# Main.net
KiCad netlist of a schematic drawn in Altium Designer
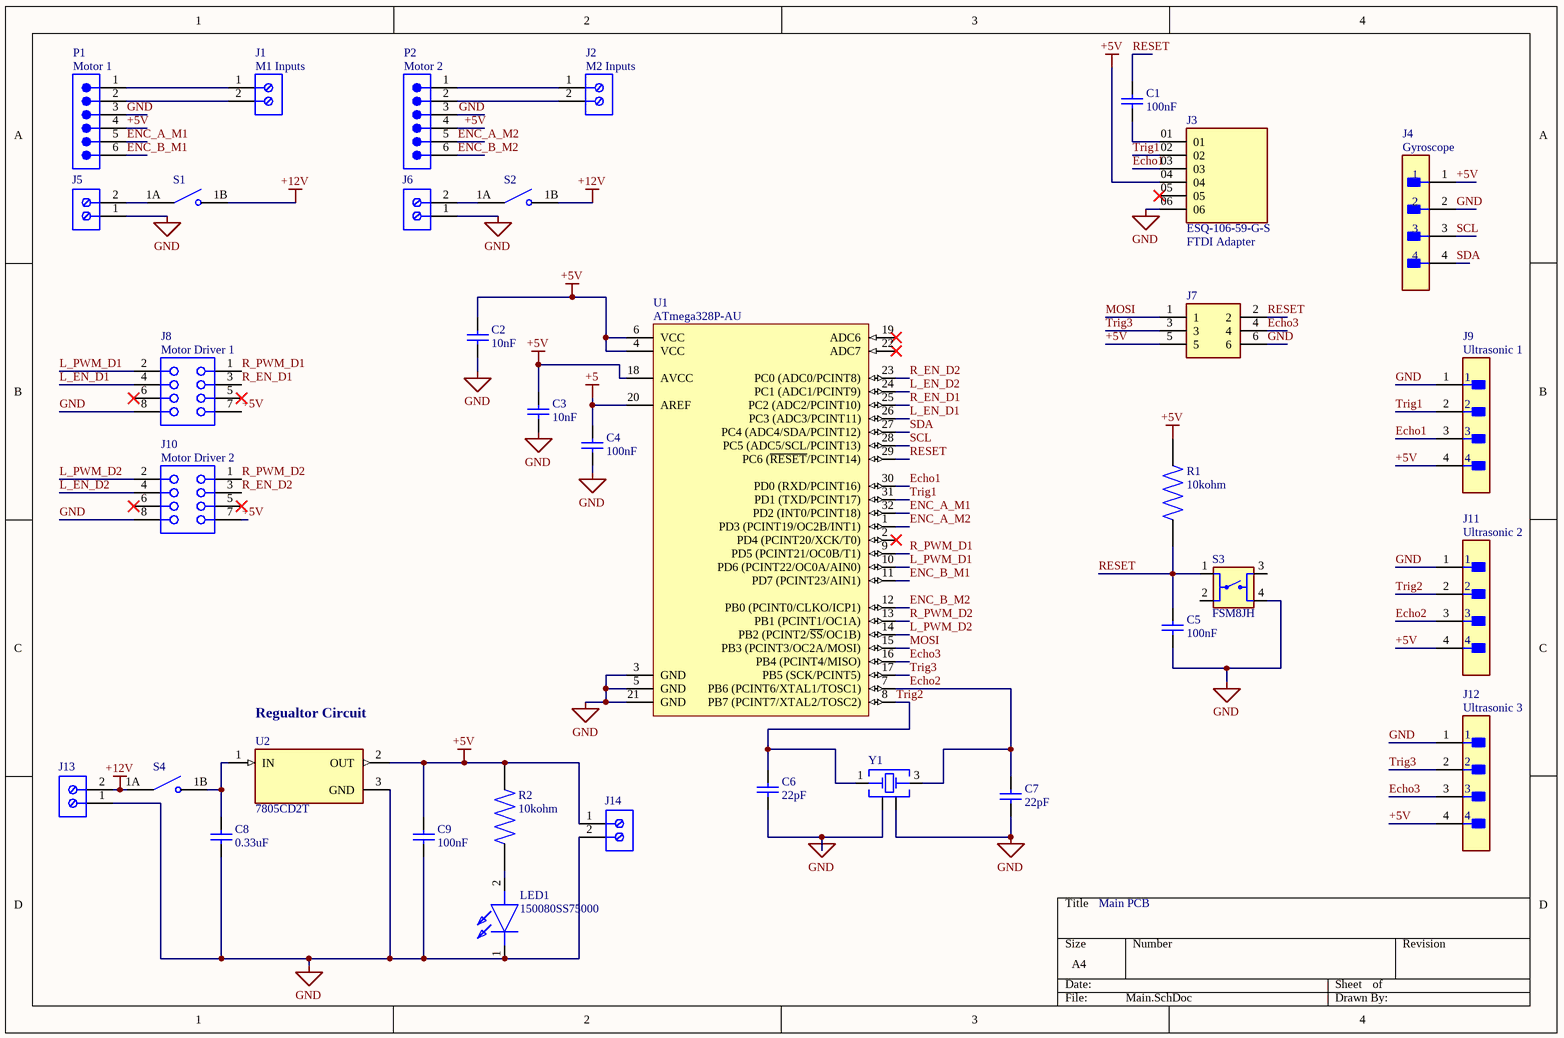
[diagram p0: Main.SchDoc]

(export (version "E")
  (design (tool "Eeschema 10.0.6"))
  (components
    (comp (ref "C1")
      (value "100nF")
      (footprint "WCAP-CSST_0603_L1.6W0.8H0.8_Reflow")
      (fields
        (field (name "MANUFACTURER PART NUMBER") "885382206004")
        (field (name "MANUFACTURER") "Wurth Elektronik")
      )
      (libsource (lib "Altium_WCAP-CSST_rev24a") (part "885382206004"))
    )
    (comp (ref "C2")
      (value "10nF")
      (footprint "WCAP-CSST_0603_L1.6W0.8H0.8_Reflow")
      (fields
        (field (name "MANUFACTURER PART NUMBER") "885382206002")
        (field (name "MANUFACTURER") "Wurth Elektronik")
      )
      (libsource (lib "Altium_WCAP-CSST_rev24a") (part "885382206002"))
    )
    (comp (ref "C3")
      (value "10nF")
      (footprint "WCAP-CSST_0603_L1.6W0.8H0.8_Reflow")
      (fields
        (field (name "MANUFACTURER PART NUMBER") "885382206002")
        (field (name "MANUFACTURER") "Wurth Elektronik")
      )
      (libsource (lib "Altium_WCAP-CSST_rev24a") (part "885382206002"))
    )
    (comp (ref "C4")
      (value "100nF")
      (footprint "WCAP-CSST_0603_L1.6W0.8H0.8_Reflow")
      (fields
        (field (name "MANUFACTURER PART NUMBER") "885382206004")
        (field (name "MANUFACTURER") "Wurth Elektronik")
      )
      (libsource (lib "Altium_WCAP-CSST_rev24a") (part "885382206004"))
    )
    (comp (ref "C5")
      (value "100nF")
      (footprint "WCAP-CSST_0603_L1.6W0.8H0.8_Reflow")
      (fields
        (field (name "MANUFACTURER PART NUMBER") "885382206004")
        (field (name "MANUFACTURER") "Wurth Elektronik")
      )
      (libsource (lib "Altium_WCAP-CSST_rev24a") (part "885382206004"))
    )
    (comp (ref "C6")
      (value "22pF")
      (footprint "WCAP-CSGP_0603_L1.6W0.8H0.8_Reflow")
      (description "WCAP-CSGP Multilayer Ceramic Chip Capacitor, General Purpose, size 0603, NP0, 22pF, 10VDC")
      (fields
        (field (name "MANUFACTURER PART NUMBER") "885012006004")
        (field (name "MANUFACTURER") "Wurth Elektronik")
      )
      (libsource (lib "Altium_WCAP-CSGP_rev24b") (part "885012006004"))
    )
    (comp (ref "C7")
      (value "22pF")
      (footprint "WCAP-CSGP_0603_L1.6W0.8H0.8_Reflow")
      (description "WCAP-CSGP Multilayer Ceramic Chip Capacitor, General Purpose, size 0603, NP0, 22pF, 10VDC")
      (fields
        (field (name "MANUFACTURER PART NUMBER") "885012006004")
        (field (name "MANUFACTURER") "Wurth Elektronik")
      )
      (libsource (lib "Altium_WCAP-CSGP_rev24b") (part "885012006004"))
    )
    (comp (ref "C8")
      (value "100nF")
      (footprint "WCAP-CSST_0603_L1.6W0.8H0.8_Reflow")
      (fields
        (field (name "MANUFACTURER PART NUMBER") "885382206004")
        (field (name "MANUFACTURER") "Wurth Elektronik")
        (field (name "CAPACITANCE") "0.33uF")
      )
      (libsource (lib "Altium_WCAP-CSST_rev24a") (part "885382206004"))
    )
    (comp (ref "C9")
      (value "100nF")
      (footprint "WCAP-CSST_0603_L1.6W0.8H0.8_Reflow")
      (fields
        (field (name "MANUFACTURER PART NUMBER") "885382206004")
        (field (name "MANUFACTURER") "Wurth Elektronik")
        (field (name "CAPACITANCE") "100nF")
      )
      (libsource (lib "Altium_WCAP-CSST_rev24a") (part "885382206004"))
    )
    (comp (ref "J1")
      (value "691137710002")
      (footprint "691137710002")
      (libsource (lib "Altium Content Vault") (part "TBL - 1R - 02P - Screw"))
    )
    (comp (ref "J2")
      (value "691137710002")
      (footprint "691137710002")
      (libsource (lib "Altium Content Vault") (part "TBL - 1R - 02P - Screw"))
    )
    (comp (ref "J3")
      (value "ESQ-106-59-G-S")
      (footprint "SAMTEC_ESQ-106-59-G-S")
      (libsource (lib "ESQ-106-59-G-S") (part "ESQ-106-59-G-S"))
    )
    (comp (ref "J4")
      (value "MPU6050")
      (footprint "FP-M20-9990445-MFG")
      (description "M20-9990445 Conn Unshrouded Header HDR 4 POS 2.54mm Solder ST Thru-Hole Bulk/Loose")
      (libsource (lib "Altium Content Vault") (part "299a8cea1bdcbc3624fe62c390fa72c"))
    )
    (comp (ref "J5")
      (value "691137710002")
      (footprint "691137710002")
      (libsource (lib "Altium Content Vault") (part "TBL - 1R - 02P - Screw"))
    )
    (comp (ref "J6")
      (value "691137710002")
      (footprint "691137710002")
      (libsource (lib "Altium Content Vault") (part "TBL - 1R - 02P - Screw"))
    )
    (comp (ref "J7")
      (value "20021111-00006T4LF")
      (footprint "SamacSys:2002111100006T4LF")
      (description "Connector")
      (libsource (lib "*") (part "20021111-00006T4LF"))
    )
    (comp (ref "J8")
      (value "Motor Driver 1")
      (footprint "SMTC-SSW-104-02-X-D")
      (description "SQ Post Socket, Through-hole, Vertical, -55 to 125 degC, 2.54mm Pitch, 8-Pin, Female, RoHS")
      (fields (field (name "MANUFACTURER") "Samtec") (field (name "PARTNUMBER") "SSW-104-02-G-D"))
      (libsource (lib "Altium Content Vault") (part "SMTC-SSW-104-X-X-D"))
    )
    (comp (ref "J9")
      (value "Ultrasonic 1")
      (footprint "FP-B4B-XH-A_LF_SN-MFG")
      (description "CONN HEADER VERT 4POS 2.5MM")
      (libsource (lib "") (part "299a8cea1bdcbc3624fe62c390fa72c_1"))
    )
    (comp (ref "J10")
      (value "Motor Driver 2")
      (footprint "SMTC-SSW-104-02-X-D")
      (description "SQ Post Socket, Through-hole, Vertical, -55 to 125 degC, 2.54mm Pitch, 8-Pin, Female, RoHS")
      (fields (field (name "MANUFACTURER") "Samtec") (field (name "PARTNUMBER") "SSW-104-02-G-D"))
      (libsource (lib "Altium Content Vault") (part "SMTC-SSW-104-X-X-D"))
    )
    (comp (ref "J11")
      (value "Ultrasonic 2")
      (footprint "FP-B4B-XH-A_LF_SN-MFG")
      (description "CONN HEADER VERT 4POS 2.5MM")
      (libsource (lib "") (part "299a8cea1bdcbc3624fe62c390fa72c_1"))
    )
    (comp (ref "J12")
      (value "Ultrasonic 3")
      (footprint "FP-B4B-XH-A_LF_SN-MFG")
      (description "CONN HEADER VERT 4POS 2.5MM")
      (libsource (lib "") (part "299a8cea1bdcbc3624fe62c390fa72c_1"))
    )
    (comp (ref "J13")
      (value "691137710002")
      (footprint "691137710002")
      (libsource (lib "Altium Content Vault") (part "TBL - 1R - 02P - Screw"))
    )
    (comp (ref "J14")
      (value "691137710002")
      (footprint "691137710002")
      (libsource (lib "Altium Content Vault") (part "TBL - 1R - 02P - Screw"))
    )
    (comp (ref "LED1")
      (value "150080SS75000")
      (footprint "SamacSys:150080SS75000")
      (description "LED")
      (fields (field (name "MOUSER PART NUMBER") "710-150080SS75000"))
      (libsource (lib "*") (part "150080SS75000"))
    )
    (comp (ref "P1")
      (value "Motor 1")
      (footprint "61300611121")
      (libsource (lib "Altium Content Vault") (part "Header_Male_1R_06P"))
    )
    (comp (ref "P2")
      (value "Motor 2")
      (footprint "61300611121")
      (libsource (lib "Altium Content Vault") (part "Header_Male_1R_06P"))
    )
    (comp (ref "R1")
      (value "10kohm")
      (footprint "RESC2012X65N")
      (fields (field (name "MP") "RMCF0805FG10K0"))
      (libsource (lib "RMCF0805FG10K0") (part "RMCF0805FG10K0"))
    )
    (comp (ref "R2")
      (value "10kohm")
      (footprint "RESC2012X65N")
      (fields (field (name "MP") "RMCF0805FG10K0"))
      (libsource (lib "RMCF0805FG10K0") (part "RMCF0805FG10K0"))
    )
    (comp (ref "S1")
      (value "DS01-254-L-01BE")
      (footprint "SW_DS01-254-L-01BE")
      (description "1 Position, Through Hole, 2.54 mm Pitch, Raised Slide Actuator, Flat Bottom, Long Pin, DIP Switch")
      (fields (field (name "MF") "CUI Devices"))
      (libsource (lib "DS01-254-L-01BE") (part "DS01-254-L-01BE"))
    )
    (comp (ref "S2")
      (value "DS01-254-L-01BE")
      (footprint "SW_DS01-254-L-01BE")
      (description "1 Position, Through Hole, 2.54 mm Pitch, Raised Slide Actuator, Flat Bottom, Long Pin, DIP Switch")
      (fields (field (name "MF") "CUI Devices"))
      (libsource (lib "DS01-254-L-01BE") (part "DS01-254-L-01BE"))
    )
    (comp (ref "S3")
      (value "FSM8JH")
      (footprint "SW_FSM8JH")
      (description "Tactile Switch SPST-NO Top Actuated Through Hole")
      (fields (field (name "MF") "TE Connectivity"))
      (libsource (lib "FSM8JH") (part "FSM8JH"))
    )
    (comp (ref "S4")
      (value "DS01-254-L-01BE")
      (footprint "SW_DS01-254-L-01BE")
      (description "1 Position, Through Hole, 2.54 mm Pitch, Raised Slide Actuator, Flat Bottom, Long Pin, DIP Switch")
      (fields (field (name "MF") "CUI Devices"))
      (libsource (lib "DS01-254-L-01BE") (part "DS01-254-L-01BE"))
    )
    (comp (ref "U1")
      (value "ATmega328P-AU")
      (footprint "32A_M")
      (libsource (lib "Altium Content Vault") (part "MC-8B-ATM48-SQ32"))
    )
    (comp (ref "U2")
      (value "7805CD2T")
      (footprint "TO254P1542X460-3N")
      (description "Linear Voltage Regulator IC Positive Fixed 1 Output 1.5A D2PAK")
      (fields (field (name "MF") "STMicroelectronics"))
      (libsource (lib "7805CD2T") (part "7805CD2T"))
    )
    (comp (ref "Y1")
      (value "830072604")
      (footprint "WE-XTAL_CFPX-180")
      (description "830072604 WE-XTAL Quartz Crystal")
      (libsource (lib "Altium Content Vault") (part "WE-XTAL_CFPX-180"))
    )
  )
  (nets
    (net (code "1") (name "+5") (class "Default")
      (node (ref "C4") (pin "2") (pinfunction "2_2") (pintype "passive"))
      (node (ref "U1") (pin "20") (pinfunction "AREF_20") (pintype "passive"))
    )
    (net (code "2") (name "+5V") (class "Default")
      (node (ref "C2") (pin "2") (pinfunction "2_2") (pintype "passive"))
      (node (ref "C3") (pin "2") (pinfunction "2_2") (pintype "passive"))
      (node (ref "C9") (pin "2") (pinfunction "2_2") (pintype "passive"))
      (node (ref "J10") (pin "7") (pinfunction "7_7") (pintype "passive"))
      (node (ref "J11") (pin "4") (pinfunction "4_4") (pintype "passive"))
      (node (ref "J12") (pin "4") (pinfunction "4_4") (pintype "passive"))
      (node (ref "J14") (pin "1") (pinfunction "1_1") (pintype "passive"))
      (node (ref "J3") (pin "04") (pinfunction "04_04") (pintype "passive"))
      (node (ref "J4") (pin "1") (pinfunction "1_1") (pintype "passive"))
      (node (ref "J7") (pin "5") (pinfunction "5_5") (pintype "passive"))
      (node (ref "J8") (pin "7") (pinfunction "7_7") (pintype "passive"))
      (node (ref "J9") (pin "4") (pinfunction "4_4") (pintype "passive"))
      (node (ref "P1") (pin "4") (pinfunction "4_4") (pintype "passive"))
      (node (ref "P2") (pin "4") (pinfunction "4_4") (pintype "passive"))
      (node (ref "R1") (pin "2") (pinfunction "2_2") (pintype "passive"))
      (node (ref "R2") (pin "2") (pinfunction "2_2") (pintype "passive"))
      (node (ref "U1") (pin "18") (pinfunction "AVCC_18") (pintype "power_in"))
      (node (ref "U1") (pin "4") (pinfunction "VCC_4") (pintype "power_in"))
      (node (ref "U1") (pin "6") (pinfunction "VCC_6") (pintype "power_in"))
      (node (ref "U2") (pin "2") (pinfunction "OUT_2") (pintype "output"))
    )
    (net (code "3") (name "+12V") (class "Default")
      (node (ref "J13") (pin "2") (pinfunction "2_2") (pintype "passive"))
      (node (ref "S1") (pin "1B") (pinfunction "NO1_1B") (pintype "passive"))
      (node (ref "S2") (pin "1B") (pinfunction "NO1_1B") (pintype "passive"))
      (node (ref "S4") (pin "1A") (pinfunction "COM1_1A") (pintype "passive"))
    )
    (net (code "4") (name "/ENC_A_M1") (class "Default")
      (node (ref "P1") (pin "5") (pinfunction "5_5") (pintype "passive"))
      (node (ref "U1") (pin "32") (pinfunction "PD2_(INT0/PCINT18)_32") (pintype "bidirectional"))
    )
    (net (code "5") (name "/ENC_A_M2") (class "Default")
      (node (ref "P2") (pin "5") (pinfunction "5_5") (pintype "passive"))
      (node (ref "U1") (pin "1") (pinfunction "PD3_(PCINT19/OC2B/INT1)_1") (pintype "bidirectional"))
    )
    (net (code "6") (name "/ENC_B_M1") (class "Default")
      (node (ref "P1") (pin "6") (pinfunction "6_6") (pintype "passive"))
      (node (ref "U1") (pin "11") (pinfunction "PD7_(PCINT23/AIN1)_11") (pintype "bidirectional"))
    )
    (net (code "7") (name "/ENC_B_M2") (class "Default")
      (node (ref "P2") (pin "6") (pinfunction "6_6") (pintype "passive"))
      (node (ref "U1") (pin "12") (pinfunction "PB0_(PCINT0/CLKO/ICP1)_12") (pintype "bidirectional"))
    )
    (net (code "8") (name "/Echo1") (class "Default")
      (node (ref "J3") (pin "03") (pinfunction "03_03") (pintype "passive"))
      (node (ref "J9") (pin "3") (pinfunction "3_3") (pintype "passive"))
      (node (ref "U1") (pin "30") (pinfunction "PD0_(RXD/PCINT16)_30") (pintype "bidirectional"))
    )
    (net (code "9") (name "/Echo2") (class "Default")
      (node (ref "C7") (pin "2") (pinfunction "2_2") (pintype "passive"))
      (node (ref "J11") (pin "3") (pinfunction "3_3") (pintype "passive"))
      (node (ref "U1") (pin "7") (pinfunction "PB6_(PCINT6/XTAL1/TOSC1)_7") (pintype "bidirectional"))
      (node (ref "Y1") (pin "3") (pinfunction "Crystal_3") (pintype "passive"))
    )
    (net (code "10") (name "/Echo3") (class "Default")
      (node (ref "J12") (pin "3") (pinfunction "3_3") (pintype "passive"))
      (node (ref "J7") (pin "4") (pinfunction "4_4") (pintype "passive"))
      (node (ref "U1") (pin "16") (pinfunction "PB4_(PCINT4/MISO)_16") (pintype "bidirectional"))
    )
    (net (code "11") (name "/L_EN_D1") (class "Default")
      (node (ref "J8") (pin "4") (pinfunction "4_4") (pintype "passive"))
      (node (ref "U1") (pin "26") (pinfunction "PC3_(ADC3/PCINT11)_26") (pintype "bidirectional"))
    )
    (net (code "12") (name "/L_EN_D2") (class "Default")
      (node (ref "J10") (pin "4") (pinfunction "4_4") (pintype "passive"))
      (node (ref "U1") (pin "24") (pinfunction "PC1_(ADC1/PCINT9)_24") (pintype "bidirectional"))
    )
    (net (code "13") (name "/L_PWM_D1") (class "Default")
      (node (ref "J8") (pin "2") (pinfunction "2_2") (pintype "passive"))
      (node (ref "U1") (pin "10") (pinfunction "PD6_(PCINT22/OC0A/AIN0)_10") (pintype "bidirectional"))
    )
    (net (code "14") (name "/L_PWM_D2") (class "Default")
      (node (ref "J10") (pin "2") (pinfunction "2_2") (pintype "passive"))
      (node (ref "U1") (pin "14") (pinfunction "PB2_(PCINT2/~{SS}/OC1B)_14") (pintype "bidirectional"))
    )
    (net (code "15") (name "/MOSI") (class "Default")
      (node (ref "J7") (pin "1") (pinfunction "1_1") (pintype "passive"))
      (node (ref "U1") (pin "15") (pinfunction "PB3_(PCINT3/OC2A/MOSI)_15") (pintype "bidirectional"))
    )
    (net (code "16") (name "/RESET") (class "Default")
      (node (ref "C1") (pin "2") (pinfunction "2_2") (pintype "passive"))
      (node (ref "C5") (pin "2") (pinfunction "2_2") (pintype "passive"))
      (node (ref "J7") (pin "2") (pinfunction "2_2") (pintype "passive"))
      (node (ref "R1") (pin "1") (pinfunction "1_1") (pintype "passive"))
      (node (ref "S3") (pin "1") (pinfunction "1_1") (pintype "passive"))
      (node (ref "U1") (pin "29") (pinfunction "PC6_(~{RESET}/PCINT14)_29") (pintype "bidirectional"))
    )
    (net (code "17") (name "/R_EN_D1") (class "Default")
      (node (ref "J8") (pin "3") (pinfunction "3_3") (pintype "passive"))
      (node (ref "U1") (pin "25") (pinfunction "PC2_(ADC2/PCINT10)_25") (pintype "bidirectional"))
    )
    (net (code "18") (name "/R_EN_D2") (class "Default")
      (node (ref "J10") (pin "3") (pinfunction "3_3") (pintype "passive"))
      (node (ref "U1") (pin "23") (pinfunction "PC0_(ADC0/PCINT8)_23") (pintype "bidirectional"))
    )
    (net (code "19") (name "/R_PWM_D1") (class "Default")
      (node (ref "J8") (pin "1") (pinfunction "1_1") (pintype "passive"))
      (node (ref "U1") (pin "9") (pinfunction "PD5_(PCINT21/OC0B/T1)_9") (pintype "bidirectional"))
    )
    (net (code "20") (name "/R_PWM_D2") (class "Default")
      (node (ref "J10") (pin "1") (pinfunction "1_1") (pintype "passive"))
      (node (ref "U1") (pin "13") (pinfunction "PB1_(PCINT1/OC1A)_13") (pintype "bidirectional"))
    )
    (net (code "21") (name "/SCL") (class "Default")
      (node (ref "J4") (pin "3") (pinfunction "3_3") (pintype "passive"))
      (node (ref "U1") (pin "28") (pinfunction "PC5_(ADC5/SCL/PCINT13)_28") (pintype "bidirectional"))
    )
    (net (code "22") (name "/SDA") (class "Default")
      (node (ref "J4") (pin "4") (pinfunction "4_4") (pintype "passive"))
      (node (ref "U1") (pin "27") (pinfunction "PC4_(ADC4/SDA/PCINT12)_27") (pintype "bidirectional"))
    )
    (net (code "23") (name "/Trig1") (class "Default")
      (node (ref "J3") (pin "02") (pinfunction "02_02") (pintype "passive"))
      (node (ref "J9") (pin "2") (pinfunction "2_2") (pintype "passive"))
      (node (ref "U1") (pin "31") (pinfunction "PD1_(TXD/PCINT17)_31") (pintype "bidirectional"))
    )
    (net (code "24") (name "/Trig2") (class "Default")
      (node (ref "C6") (pin "2") (pinfunction "2_2") (pintype "passive"))
      (node (ref "J11") (pin "2") (pinfunction "2_2") (pintype "passive"))
      (node (ref "U1") (pin "8") (pinfunction "PB7_(PCINT7/XTAL2/TOSC2)_8") (pintype "bidirectional"))
      (node (ref "Y1") (pin "1") (pinfunction "Crystal_1") (pintype "passive"))
    )
    (net (code "25") (name "/Trig3") (class "Default")
      (node (ref "J12") (pin "2") (pinfunction "2_2") (pintype "passive"))
      (node (ref "J7") (pin "3") (pinfunction "3_3") (pintype "passive"))
      (node (ref "U1") (pin "17") (pinfunction "PB5_(SCK/PCINT5)_17") (pintype "bidirectional"))
    )
    (net (code "26") (name "GND") (class "Default")
      (node (ref "C2") (pin "1") (pinfunction "1_1") (pintype "passive"))
      (node (ref "C3") (pin "1") (pinfunction "1_1") (pintype "passive"))
      (node (ref "C4") (pin "1") (pinfunction "1_1") (pintype "passive"))
      (node (ref "C5") (pin "1") (pinfunction "1_1") (pintype "passive"))
      (node (ref "C6") (pin "1") (pinfunction "1_1") (pintype "passive"))
      (node (ref "C7") (pin "1") (pinfunction "1_1") (pintype "passive"))
      (node (ref "C8") (pin "1") (pinfunction "1_1") (pintype "passive"))
      (node (ref "C9") (pin "1") (pinfunction "1_1") (pintype "passive"))
      (node (ref "J10") (pin "8") (pinfunction "8_8") (pintype "passive"))
      (node (ref "J11") (pin "1") (pinfunction "1_1") (pintype "passive"))
      (node (ref "J12") (pin "1") (pinfunction "1_1") (pintype "passive"))
      (node (ref "J13") (pin "1") (pinfunction "1_1") (pintype "passive"))
      (node (ref "J14") (pin "2") (pinfunction "2_2") (pintype "passive"))
      (node (ref "J3") (pin "06") (pinfunction "06_06") (pintype "passive"))
      (node (ref "J4") (pin "2") (pinfunction "2_2") (pintype "passive"))
      (node (ref "J5") (pin "1") (pinfunction "1_1") (pintype "passive"))
      (node (ref "J6") (pin "1") (pinfunction "1_1") (pintype "passive"))
      (node (ref "J7") (pin "6") (pinfunction "6_6") (pintype "passive"))
      (node (ref "J8") (pin "8") (pinfunction "8_8") (pintype "passive"))
      (node (ref "J9") (pin "1") (pinfunction "1_1") (pintype "passive"))
      (node (ref "LED1") (pin "1") (pinfunction "K_1") (pintype "passive"))
      (node (ref "P1") (pin "3") (pinfunction "3_3") (pintype "passive"))
      (node (ref "P2") (pin "3") (pinfunction "3_3") (pintype "passive"))
      (node (ref "S3") (pin "4") (pinfunction "4_4") (pintype "passive"))
      (node (ref "U1") (pin "21") (pinfunction "GND_21") (pintype "power_in"))
      (node (ref "U1") (pin "3") (pinfunction "GND_3") (pintype "power_in"))
      (node (ref "U1") (pin "5") (pinfunction "GND_5") (pintype "power_in"))
      (node (ref "U2") (pin "3") (pinfunction "GND_3") (pintype "power_in"))
      (node (ref "Y1") (pin "2") (pinfunction "GND&Lid_2") (pintype "passive"))
      (node (ref "Y1") (pin "4") (pinfunction "GND&Lid_4") (pintype "passive"))
    )
    (net (code "27") (name "Net-(C1-Pad1)") (class "Default")
      (node (ref "C1") (pin "1") (pinfunction "1_1") (pintype "passive"))
      (node (ref "J3") (pin "01") (pinfunction "01_01") (pintype "passive"))
    )
    (net (code "28") (name "Net-(J1-Pad1)") (class "Default")
      (node (ref "J1") (pin "1") (pinfunction "1_1") (pintype "passive"))
      (node (ref "P1") (pin "1") (pinfunction "1_1") (pintype "passive"))
    )
    (net (code "29") (name "Net-(J1-Pad2)") (class "Default")
      (node (ref "J1") (pin "2") (pinfunction "2_2") (pintype "passive"))
      (node (ref "P1") (pin "2") (pinfunction "2_2") (pintype "passive"))
    )
    (net (code "30") (name "Net-(J2-Pad1)") (class "Default")
      (node (ref "J2") (pin "1") (pinfunction "1_1") (pintype "passive"))
      (node (ref "P2") (pin "1") (pinfunction "1_1") (pintype "passive"))
    )
    (net (code "31") (name "Net-(J2-Pad2)") (class "Default")
      (node (ref "J2") (pin "2") (pinfunction "2_2") (pintype "passive"))
      (node (ref "P2") (pin "2") (pinfunction "2_2") (pintype "passive"))
    )
    (net (code "32") (name "Net-(LED1-A)") (class "Default")
      (node (ref "LED1") (pin "2") (pinfunction "A_2") (pintype "passive"))
      (node (ref "R2") (pin "1") (pinfunction "1_1") (pintype "passive"))
    )
    (net (code "33") (name "Net-(S1-COM1)") (class "Default")
      (node (ref "J5") (pin "2") (pinfunction "2_2") (pintype "passive"))
      (node (ref "S1") (pin "1A") (pinfunction "COM1_1A") (pintype "passive"))
    )
    (net (code "34") (name "Net-(S2-COM1)") (class "Default")
      (node (ref "J6") (pin "2") (pinfunction "2_2") (pintype "passive"))
      (node (ref "S2") (pin "1A") (pinfunction "COM1_1A") (pintype "passive"))
    )
    (net (code "35") (name "Net-(S4-NO1)") (class "Default")
      (node (ref "C8") (pin "2") (pinfunction "2_2") (pintype "passive"))
      (node (ref "S4") (pin "1B") (pinfunction "NO1_1B") (pintype "passive"))
      (node (ref "U2") (pin "1") (pinfunction "IN_1") (pintype "input"))
    )
    (net (code "36") (name "unconnected-(J3-Pad05)") (class "Default")
      (node (ref "J3") (pin "05") (pinfunction "05_05") (pintype "passive+no_connect"))
    )
    (net (code "37") (name "unconnected-(J8-Pad5)") (class "Default")
      (node (ref "J8") (pin "5") (pinfunction "5_5") (pintype "passive+no_connect"))
    )
    (net (code "38") (name "unconnected-(J8-Pad6)") (class "Default")
      (node (ref "J8") (pin "6") (pinfunction "6_6") (pintype "passive+no_connect"))
    )
    (net (code "39") (name "unconnected-(J10-Pad5)") (class "Default")
      (node (ref "J10") (pin "5") (pinfunction "5_5") (pintype "passive+no_connect"))
    )
    (net (code "40") (name "unconnected-(J10-Pad6)") (class "Default")
      (node (ref "J10") (pin "6") (pinfunction "6_6") (pintype "passive+no_connect"))
    )
    (net (code "41") (name "unconnected-(S3-Pad2)") (class "Default")
      (node (ref "S3") (pin "2") (pinfunction "2_2") (pintype "passive"))
    )
    (net (code "42") (name "unconnected-(S3-Pad3)") (class "Default")
      (node (ref "S3") (pin "3") (pinfunction "3_3") (pintype "passive"))
    )
    (net (code "43") (name "unconnected-(U1-ADC6-Pad19)") (class "Default")
      (node (ref "U1") (pin "19") (pinfunction "ADC6_19") (pintype "input+no_connect"))
    )
    (net (code "44") (name "unconnected-(U1-ADC7-Pad22)") (class "Default")
      (node (ref "U1") (pin "22") (pinfunction "ADC7_22") (pintype "input+no_connect"))
    )
    (net (code "45") (name "unconnected-(U1-PD4_(PCINT20{slash}XCK{slash}T0)-Pad2)") (class "Default")
      (node (ref "U1") (pin "2") (pinfunction "PD4_(PCINT20/XCK/T0)_2") (pintype "bidirectional+no_connect"))
    )
  )
)
